# hand_brd.net
KiCad netlist of a schematic drawn in EAGLE
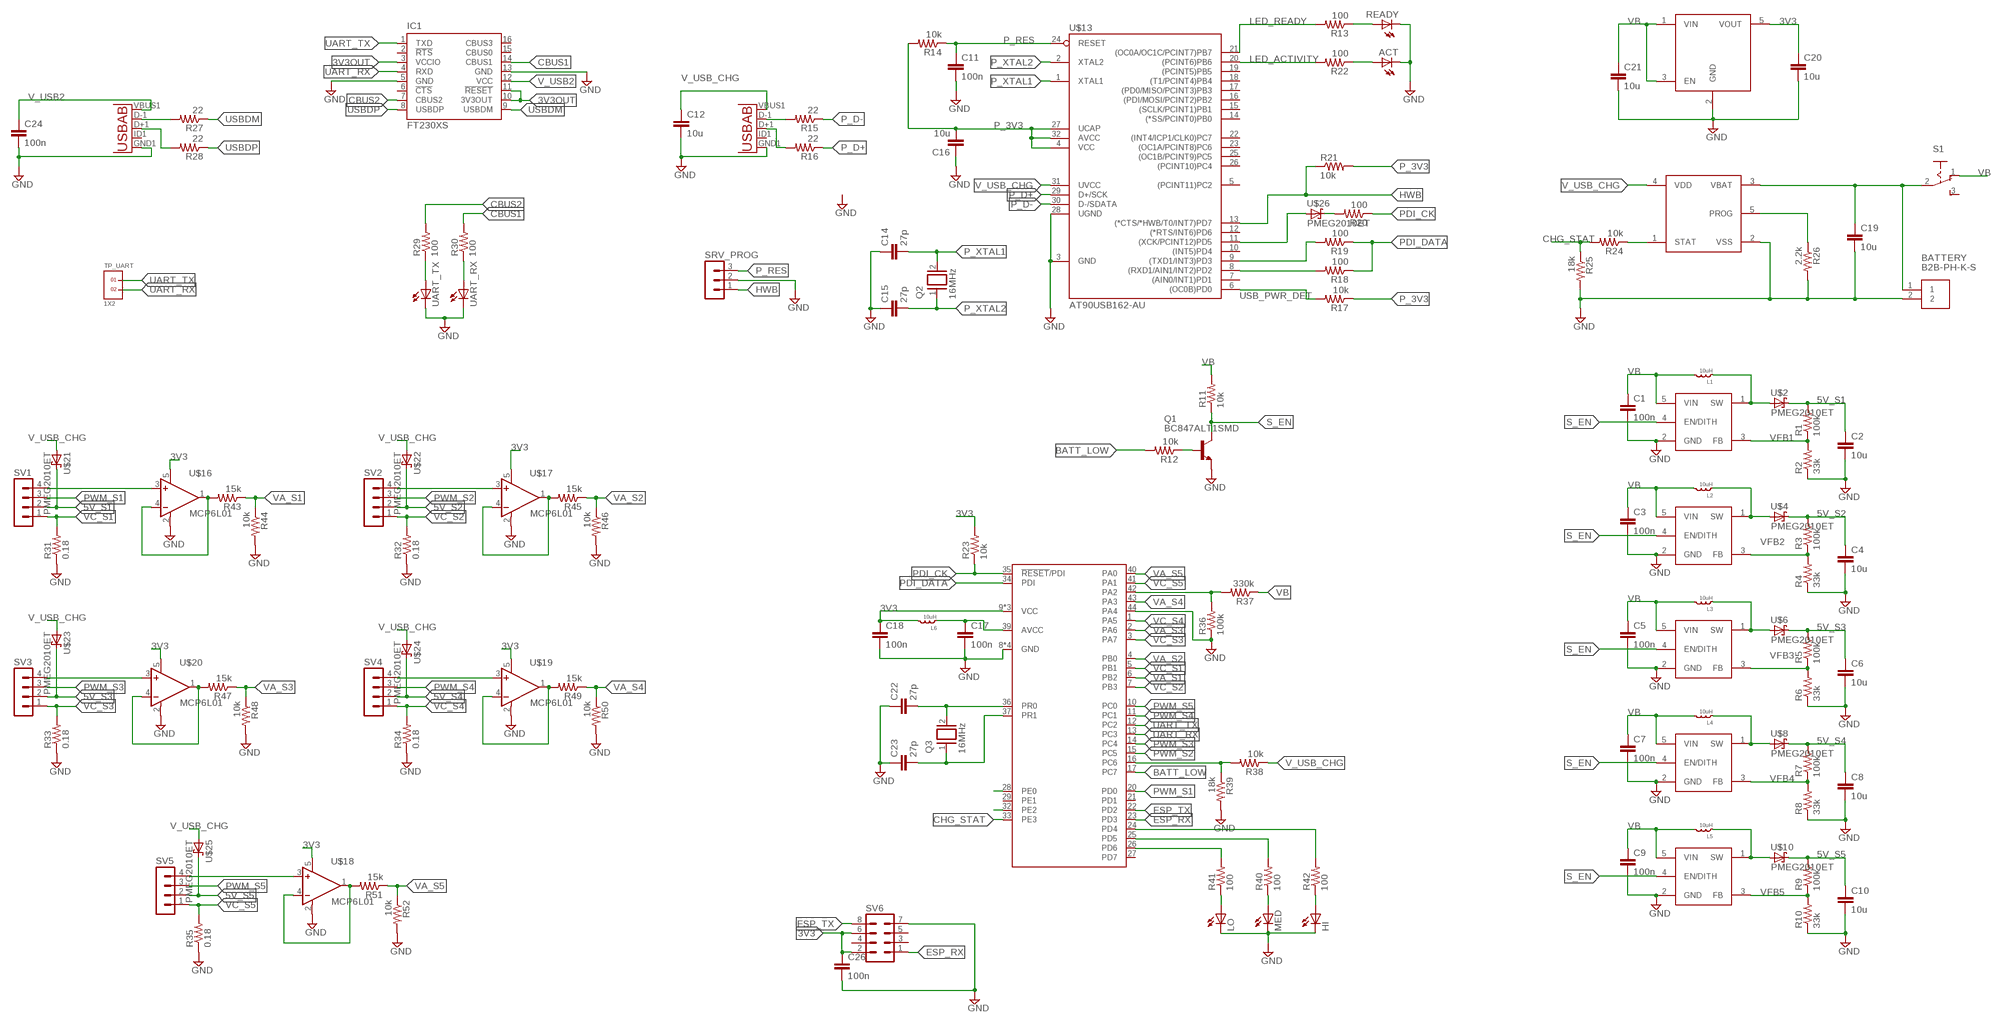
[diagram p0: schematic, sheet 1]

(export (version "E")
  (design (tool "Eeschema 10.0.6"))
  (components
    (comp (ref "ACT")
      (value "LEDCHIPLED_0805")
      (footprint "eagle-import:CHIPLED_0805")
      (libsource (lib "eagle-import") (part "LEDCHIPLED_0805"))
    )
    (comp (ref "BATTERY")
      (value "B2B-PH-K-S")
      (footprint "eagle-import:B2B-PH-K-S")
      (libsource (lib "eagle-import") (part "B2B-PH-K-S"))
    )
    (comp (ref "C1")
      (value "100n")
      (footprint "eagle-import:C0805K")
      (libsource (lib "eagle-import") (part "C-EUC0805K"))
    )
    (comp (ref "C2")
      (value "10u")
      (footprint "eagle-import:C0805K")
      (libsource (lib "eagle-import") (part "C-EUC0805K"))
    )
    (comp (ref "C3")
      (value "100n")
      (footprint "eagle-import:C0805K")
      (libsource (lib "eagle-import") (part "C-EUC0805K"))
    )
    (comp (ref "C4")
      (value "10u")
      (footprint "eagle-import:C0805K")
      (libsource (lib "eagle-import") (part "C-EUC0805K"))
    )
    (comp (ref "C5")
      (value "100n")
      (footprint "eagle-import:C0805K")
      (libsource (lib "eagle-import") (part "C-EUC0805K"))
    )
    (comp (ref "C6")
      (value "10u")
      (footprint "eagle-import:C0805K")
      (libsource (lib "eagle-import") (part "C-EUC0805K"))
    )
    (comp (ref "C7")
      (value "100n")
      (footprint "eagle-import:C0805K")
      (libsource (lib "eagle-import") (part "C-EUC0805K"))
    )
    (comp (ref "C8")
      (value "10u")
      (footprint "eagle-import:C0805K")
      (libsource (lib "eagle-import") (part "C-EUC0805K"))
    )
    (comp (ref "C9")
      (value "100n")
      (footprint "eagle-import:C0805K")
      (libsource (lib "eagle-import") (part "C-EUC0805K"))
    )
    (comp (ref "C10")
      (value "10u")
      (footprint "eagle-import:C0805K")
      (libsource (lib "eagle-import") (part "C-EUC0805K"))
    )
    (comp (ref "C11")
      (value "100n")
      (footprint "eagle-import:C0805K")
      (libsource (lib "eagle-import") (part "C-EUC0805K"))
    )
    (comp (ref "C12")
      (value "10u")
      (footprint "eagle-import:C0805K")
      (libsource (lib "eagle-import") (part "C-EUC0805K"))
    )
    (comp (ref "C14")
      (value "27p")
      (footprint "eagle-import:C0805K")
      (libsource (lib "eagle-import") (part "C-EUC0805K"))
    )
    (comp (ref "C15")
      (value "27p")
      (footprint "eagle-import:C0805K")
      (libsource (lib "eagle-import") (part "C-EUC0805K"))
    )
    (comp (ref "C16")
      (value "10u")
      (footprint "eagle-import:C0805K")
      (libsource (lib "eagle-import") (part "C-EUC0805K"))
    )
    (comp (ref "C17")
      (value "100n")
      (footprint "eagle-import:C0805K")
      (libsource (lib "eagle-import") (part "C-EUC0805K"))
    )
    (comp (ref "C18")
      (value "100n")
      (footprint "eagle-import:C0805K")
      (libsource (lib "eagle-import") (part "C-EUC0805K"))
    )
    (comp (ref "C19")
      (value "10u")
      (footprint "eagle-import:C0805K")
      (libsource (lib "eagle-import") (part "C-EUC0805K"))
    )
    (comp (ref "C20")
      (value "10u")
      (footprint "eagle-import:C0805K")
      (libsource (lib "eagle-import") (part "C-EUC0805K"))
    )
    (comp (ref "C21")
      (value "10u")
      (footprint "eagle-import:C0805K")
      (libsource (lib "eagle-import") (part "C-EUC0805K"))
    )
    (comp (ref "C22")
      (value "27p")
      (footprint "eagle-import:C0805K")
      (libsource (lib "eagle-import") (part "C-EUC0805K"))
    )
    (comp (ref "C23")
      (value "27p")
      (footprint "eagle-import:C0805K")
      (libsource (lib "eagle-import") (part "C-EUC0805K"))
    )
    (comp (ref "C24")
      (value "100n")
      (footprint "eagle-import:C0805K")
      (libsource (lib "eagle-import") (part "C-EUC0805K"))
    )
    (comp (ref "C26")
      (value "100n")
      (footprint "eagle-import:C0805K")
      (libsource (lib "eagle-import") (part "C-EUC0805K"))
    )
    (comp (ref "HI")
      (value "LEDCHIPLED_0805")
      (footprint "eagle-import:CHIPLED_0805")
      (libsource (lib "eagle-import") (part "LEDCHIPLED_0805"))
    )
    (comp (ref "IC1")
      (value "FT230XS")
      (footprint "eagle-import:SSOP16")
      (libsource (lib "eagle-import") (part "FT230XS"))
    )
    (comp (ref "L1")
      (value "10uH")
      (footprint "eagle-import:LTF5022")
      (libsource (lib "eagle-import") (part "L_TDK_LTF5022"))
    )
    (comp (ref "L2")
      (value "10uH")
      (footprint "eagle-import:LTF5022")
      (libsource (lib "eagle-import") (part "L_TDK_LTF5022"))
    )
    (comp (ref "L3")
      (value "10uH")
      (footprint "eagle-import:LTF5022")
      (libsource (lib "eagle-import") (part "L_TDK_LTF5022"))
    )
    (comp (ref "L4")
      (value "10uH")
      (footprint "eagle-import:LTF5022")
      (libsource (lib "eagle-import") (part "L_TDK_LTF5022"))
    )
    (comp (ref "L5")
      (value "10uH")
      (footprint "eagle-import:LTF5022")
      (libsource (lib "eagle-import") (part "L_TDK_LTF5022"))
    )
    (comp (ref "L6")
      (value "10uH")
      (footprint "eagle-import:LTF5022")
      (libsource (lib "eagle-import") (part "L_TDK_LTF5022"))
    )
    (comp (ref "LO")
      (value "LEDCHIPLED_0805")
      (footprint "eagle-import:CHIPLED_0805")
      (libsource (lib "eagle-import") (part "LEDCHIPLED_0805"))
    )
    (comp (ref "MED")
      (value "LEDCHIPLED_0805")
      (footprint "eagle-import:CHIPLED_0805")
      (libsource (lib "eagle-import") (part "LEDCHIPLED_0805"))
    )
    (comp (ref "Q1")
      (value "BC847ALT1SMD")
      (footprint "eagle-import:SOT23")
      (libsource (lib "eagle-import") (part "BC847SMDALT1"))
    )
    (comp (ref "Q2")
      (value "16MHz")
      (footprint "eagle-import:QS")
      (libsource (lib "eagle-import") (part "XTAL/S"))
    )
    (comp (ref "Q3")
      (value "16MHz")
      (footprint "eagle-import:QS")
      (libsource (lib "eagle-import") (part "XTAL/S"))
    )
    (comp (ref "R1")
      (value "100k")
      (footprint "eagle-import:M0805")
      (libsource (lib "eagle-import") (part "R-US_M0805"))
    )
    (comp (ref "R2")
      (value "33k")
      (footprint "eagle-import:M0805")
      (libsource (lib "eagle-import") (part "R-US_M0805"))
    )
    (comp (ref "R3")
      (value "100k")
      (footprint "eagle-import:M0805")
      (libsource (lib "eagle-import") (part "R-US_M0805"))
    )
    (comp (ref "R4")
      (value "33k")
      (footprint "eagle-import:M0805")
      (libsource (lib "eagle-import") (part "R-US_M0805"))
    )
    (comp (ref "R5")
      (value "100k")
      (footprint "eagle-import:M0805")
      (libsource (lib "eagle-import") (part "R-US_M0805"))
    )
    (comp (ref "R6")
      (value "33k")
      (footprint "eagle-import:M0805")
      (libsource (lib "eagle-import") (part "R-US_M0805"))
    )
    (comp (ref "R7")
      (value "100k")
      (footprint "eagle-import:M0805")
      (libsource (lib "eagle-import") (part "R-US_M0805"))
    )
    (comp (ref "R8")
      (value "33k")
      (footprint "eagle-import:M0805")
      (libsource (lib "eagle-import") (part "R-US_M0805"))
    )
    (comp (ref "R9")
      (value "100k")
      (footprint "eagle-import:M0805")
      (libsource (lib "eagle-import") (part "R-US_M0805"))
    )
    (comp (ref "R10")
      (value "33k")
      (footprint "eagle-import:M0805")
      (libsource (lib "eagle-import") (part "R-US_M0805"))
    )
    (comp (ref "R11")
      (value "10k")
      (footprint "eagle-import:M0805")
      (libsource (lib "eagle-import") (part "R-US_M0805"))
    )
    (comp (ref "R12")
      (value "10k")
      (footprint "eagle-import:M0805")
      (libsource (lib "eagle-import") (part "R-US_M0805"))
    )
    (comp (ref "R13")
      (value "100")
      (footprint "eagle-import:M0805")
      (libsource (lib "eagle-import") (part "R-US_M0805"))
    )
    (comp (ref "R14")
      (value "10k")
      (footprint "eagle-import:M0805")
      (libsource (lib "eagle-import") (part "R-US_M0805"))
    )
    (comp (ref "R15")
      (value "22")
      (footprint "eagle-import:M0805")
      (libsource (lib "eagle-import") (part "R-US_M0805"))
    )
    (comp (ref "R16")
      (value "22")
      (footprint "eagle-import:M0805")
      (libsource (lib "eagle-import") (part "R-US_M0805"))
    )
    (comp (ref "R17")
      (value "10k")
      (footprint "eagle-import:M0805")
      (libsource (lib "eagle-import") (part "R-US_M0805"))
    )
    (comp (ref "R18")
      (value "100")
      (footprint "eagle-import:M0805")
      (libsource (lib "eagle-import") (part "R-US_M0805"))
    )
    (comp (ref "R19")
      (value "100")
      (footprint "eagle-import:M0805")
      (libsource (lib "eagle-import") (part "R-US_M0805"))
    )
    (comp (ref "R20")
      (value "100")
      (footprint "eagle-import:M0805")
      (libsource (lib "eagle-import") (part "R-US_M0805"))
    )
    (comp (ref "R21")
      (value "10k")
      (footprint "eagle-import:M0805")
      (libsource (lib "eagle-import") (part "R-US_M0805"))
    )
    (comp (ref "R22")
      (value "100")
      (footprint "eagle-import:M0805")
      (libsource (lib "eagle-import") (part "R-US_M0805"))
    )
    (comp (ref "R23")
      (value "10k")
      (footprint "eagle-import:M0805")
      (libsource (lib "eagle-import") (part "R-US_M0805"))
    )
    (comp (ref "R24")
      (value "10k")
      (footprint "eagle-import:M0805")
      (libsource (lib "eagle-import") (part "R-US_M0805"))
    )
    (comp (ref "R25")
      (value "18k")
      (footprint "eagle-import:M0805")
      (libsource (lib "eagle-import") (part "R-US_M0805"))
    )
    (comp (ref "R26")
      (value "2.2k")
      (footprint "eagle-import:M0805")
      (libsource (lib "eagle-import") (part "R-US_M0805"))
    )
    (comp (ref "R27")
      (value "22")
      (footprint "eagle-import:M0805")
      (libsource (lib "eagle-import") (part "R-US_M0805"))
    )
    (comp (ref "R28")
      (value "22")
      (footprint "eagle-import:M0805")
      (libsource (lib "eagle-import") (part "R-US_M0805"))
    )
    (comp (ref "R29")
      (value "100")
      (footprint "eagle-import:M0805")
      (libsource (lib "eagle-import") (part "R-US_M0805"))
    )
    (comp (ref "R30")
      (value "100")
      (footprint "eagle-import:M0805")
      (libsource (lib "eagle-import") (part "R-US_M0805"))
    )
    (comp (ref "R31")
      (value "0.18")
      (footprint "eagle-import:M0805")
      (libsource (lib "eagle-import") (part "R-US_M0805"))
    )
    (comp (ref "R32")
      (value "0.18")
      (footprint "eagle-import:M0805")
      (libsource (lib "eagle-import") (part "R-US_M0805"))
    )
    (comp (ref "R33")
      (value "0.18")
      (footprint "eagle-import:M0805")
      (libsource (lib "eagle-import") (part "R-US_M0805"))
    )
    (comp (ref "R34")
      (value "0.18")
      (footprint "eagle-import:M0805")
      (libsource (lib "eagle-import") (part "R-US_M0805"))
    )
    (comp (ref "R35")
      (value "0.18")
      (footprint "eagle-import:M0805")
      (libsource (lib "eagle-import") (part "R-US_M0805"))
    )
    (comp (ref "R36")
      (value "100k")
      (footprint "eagle-import:M0805")
      (libsource (lib "eagle-import") (part "R-US_M0805"))
    )
    (comp (ref "R37")
      (value "330k")
      (footprint "eagle-import:M0805")
      (libsource (lib "eagle-import") (part "R-US_M0805"))
    )
    (comp (ref "R38")
      (value "10k")
      (footprint "eagle-import:M0805")
      (libsource (lib "eagle-import") (part "R-US_M0805"))
    )
    (comp (ref "R39")
      (value "18k")
      (footprint "eagle-import:M0805")
      (libsource (lib "eagle-import") (part "R-US_M0805"))
    )
    (comp (ref "R40")
      (value "100")
      (footprint "eagle-import:M0805")
      (libsource (lib "eagle-import") (part "R-US_M0805"))
    )
    (comp (ref "R41")
      (value "100")
      (footprint "eagle-import:M0805")
      (libsource (lib "eagle-import") (part "R-US_M0805"))
    )
    (comp (ref "R42")
      (value "100")
      (footprint "eagle-import:M0805")
      (libsource (lib "eagle-import") (part "R-US_M0805"))
    )
    (comp (ref "R43")
      (value "15k")
      (footprint "eagle-import:M0805")
      (libsource (lib "eagle-import") (part "R-US_M0805"))
    )
    (comp (ref "R44")
      (value "10k")
      (footprint "eagle-import:M0805")
      (libsource (lib "eagle-import") (part "R-US_M0805"))
    )
    (comp (ref "R45")
      (value "15k")
      (footprint "eagle-import:M0805")
      (libsource (lib "eagle-import") (part "R-US_M0805"))
    )
    (comp (ref "R46")
      (value "10k")
      (footprint "eagle-import:M0805")
      (libsource (lib "eagle-import") (part "R-US_M0805"))
    )
    (comp (ref "R47")
      (value "15k")
      (footprint "eagle-import:M0805")
      (libsource (lib "eagle-import") (part "R-US_M0805"))
    )
    (comp (ref "R48")
      (value "10k")
      (footprint "eagle-import:M0805")
      (libsource (lib "eagle-import") (part "R-US_M0805"))
    )
    (comp (ref "R49")
      (value "15k")
      (footprint "eagle-import:M0805")
      (libsource (lib "eagle-import") (part "R-US_M0805"))
    )
    (comp (ref "R50")
      (value "10k")
      (footprint "eagle-import:M0805")
      (libsource (lib "eagle-import") (part "R-US_M0805"))
    )
    (comp (ref "R51")
      (value "15k")
      (footprint "eagle-import:M0805")
      (libsource (lib "eagle-import") (part "R-US_M0805"))
    )
    (comp (ref "R52")
      (value "10k")
      (footprint "eagle-import:M0805")
      (libsource (lib "eagle-import") (part "R-US_M0805"))
    )
    (comp (ref "READY")
      (value "LEDCHIPLED_0805")
      (footprint "eagle-import:CHIPLED_0805")
      (libsource (lib "eagle-import") (part "LEDCHIPLED_0805"))
    )
    (comp (ref "S1")
      (value "255SB")
      (footprint "eagle-import:255SB")
      (libsource (lib "eagle-import") (part "255SB"))
    )
    (comp (ref "SRV_PROG")
      (value "MA03-1")
      (footprint "eagle-import:MA03-1")
      (libsource (lib "eagle-import") (part "MA03-1"))
    )
    (comp (ref "SV1")
      (value "MA04-1")
      (footprint "eagle-import:MA04-1")
      (libsource (lib "eagle-import") (part "MA04-1"))
    )
    (comp (ref "SV2")
      (value "MA04-1")
      (footprint "eagle-import:MA04-1")
      (libsource (lib "eagle-import") (part "MA04-1"))
    )
    (comp (ref "SV3")
      (value "MA04-1")
      (footprint "eagle-import:MA04-1")
      (libsource (lib "eagle-import") (part "MA04-1"))
    )
    (comp (ref "SV4")
      (value "MA04-1")
      (footprint "eagle-import:MA04-1")
      (libsource (lib "eagle-import") (part "MA04-1"))
    )
    (comp (ref "SV5")
      (value "MA04-1")
      (footprint "eagle-import:MA04-1")
      (libsource (lib "eagle-import") (part "MA04-1"))
    )
    (comp (ref "SV6")
      (value "MA04-2")
      (footprint "eagle-import:MA04-2")
      (libsource (lib "eagle-import") (part "MA04-2"))
    )
    (comp (ref "TP_UART")
      (value "1X2")
      (footprint "eagle-import:1X2")
      (libsource (lib "eagle-import") (part "1X2"))
    )
    (comp (ref "U$1")
      (value "MIC2250-2YD5")
      (footprint "eagle-import:SOT23-5")
      (libsource (lib "eagle-import") (part "MIC2250-2YD5"))
    )
    (comp (ref "U$2")
      (value "PMEG2010ET")
      (footprint "eagle-import:SOT23")
      (libsource (lib "eagle-import") (part "PMEG2010ET"))
    )
    (comp (ref "U$3")
      (value "MIC2250-2YD5")
      (footprint "eagle-import:SOT23-5")
      (libsource (lib "eagle-import") (part "MIC2250-2YD5"))
    )
    (comp (ref "U$4")
      (value "PMEG2010ET")
      (footprint "eagle-import:SOT23")
      (libsource (lib "eagle-import") (part "PMEG2010ET"))
    )
    (comp (ref "U$5")
      (value "MIC2250-2YD5")
      (footprint "eagle-import:SOT23-5")
      (libsource (lib "eagle-import") (part "MIC2250-2YD5"))
    )
    (comp (ref "U$6")
      (value "PMEG2010ET")
      (footprint "eagle-import:SOT23")
      (libsource (lib "eagle-import") (part "PMEG2010ET"))
    )
    (comp (ref "U$7")
      (value "MIC2250-2YD5")
      (footprint "eagle-import:SOT23-5")
      (libsource (lib "eagle-import") (part "MIC2250-2YD5"))
    )
    (comp (ref "U$8")
      (value "PMEG2010ET")
      (footprint "eagle-import:SOT23")
      (libsource (lib "eagle-import") (part "PMEG2010ET"))
    )
    (comp (ref "U$9")
      (value "MIC2250-2YD5")
      (footprint "eagle-import:SOT23-5")
      (libsource (lib "eagle-import") (part "MIC2250-2YD5"))
    )
    (comp (ref "U$10")
      (value "PMEG2010ET")
      (footprint "eagle-import:SOT23")
      (libsource (lib "eagle-import") (part "PMEG2010ET"))
    )
    (comp (ref "U$13")
      (value "AT90USB162-AU")
      (footprint "eagle-import:TQFP32-08")
      (libsource (lib "eagle-import") (part "AT90USB162-AU"))
    )
    (comp (ref "U$14")
      (value "MCP73831")
      (footprint "eagle-import:SOT23-5")
      (libsource (lib "eagle-import") (part "MCP73831"))
    )
    (comp (ref "U$15")
      (value "MIC5504")
      (footprint "eagle-import:SOT23-5")
      (libsource (lib "eagle-import") (part "MIC5504"))
    )
    (comp (ref "U$16")
      (value "MCP6L01")
      (footprint "eagle-import:SOT23-5")
      (libsource (lib "eagle-import") (part "MCP6L01"))
    )
    (comp (ref "U$17")
      (value "MCP6L01")
      (footprint "eagle-import:SOT23-5")
      (libsource (lib "eagle-import") (part "MCP6L01"))
    )
    (comp (ref "U$18")
      (value "MCP6L01")
      (footprint "eagle-import:SOT23-5")
      (libsource (lib "eagle-import") (part "MCP6L01"))
    )
    (comp (ref "U$19")
      (value "MCP6L01")
      (footprint "eagle-import:SOT23-5")
      (libsource (lib "eagle-import") (part "MCP6L01"))
    )
    (comp (ref "U$20")
      (value "MCP6L01")
      (footprint "eagle-import:SOT23-5")
      (libsource (lib "eagle-import") (part "MCP6L01"))
    )
    (comp (ref "U$21")
      (value "PMEG2010ET")
      (footprint "eagle-import:SOT23")
      (libsource (lib "eagle-import") (part "PMEG2010ET"))
    )
    (comp (ref "U$22")
      (value "PMEG2010ET")
      (footprint "eagle-import:SOT23")
      (libsource (lib "eagle-import") (part "PMEG2010ET"))
    )
    (comp (ref "U$23")
      (value "PMEG2010ET")
      (footprint "eagle-import:SOT23")
      (libsource (lib "eagle-import") (part "PMEG2010ET"))
    )
    (comp (ref "U$24")
      (value "PMEG2010ET")
      (footprint "eagle-import:SOT23")
      (libsource (lib "eagle-import") (part "PMEG2010ET"))
    )
    (comp (ref "U$25")
      (value "PMEG2010ET")
      (footprint "eagle-import:SOT23")
      (libsource (lib "eagle-import") (part "PMEG2010ET"))
    )
    (comp (ref "U$26")
      (value "PMEG2010ET")
      (footprint "eagle-import:SOT23")
      (libsource (lib "eagle-import") (part "PMEG2010ET"))
    )
    (comp (ref "U1")
      (value "USB\"\"")
      (footprint "eagle-import:USB-MICRO-SMD")
      (libsource (lib "eagle-import") (part "USB{dblquote}{dblquote}"))
    )
    (comp (ref "U2")
      (value "ATXMEGA128D4-AU")
      (footprint "eagle-import:TQFP-44A-44")
      (libsource (lib "eagle-import") (part "ATXMEGA128D4-AU"))
    )
    (comp (ref "U3")
      (value "USB\"\"")
      (footprint "eagle-import:USB-MICRO-SMD")
      (libsource (lib "eagle-import") (part "USB{dblquote}{dblquote}"))
    )
    (comp (ref "UART_RX")
      (value "LEDCHIPLED_0805")
      (footprint "eagle-import:CHIPLED_0805")
      (libsource (lib "eagle-import") (part "LEDCHIPLED_0805"))
    )
    (comp (ref "UART_TX")
      (value "LEDCHIPLED_0805")
      (footprint "eagle-import:CHIPLED_0805")
      (libsource (lib "eagle-import") (part "LEDCHIPLED_0805"))
    )
  )
  (nets
    (net (code "1") (name "/LED_ACTIVITY") (class "Default")
      (node (ref "R22") (pin "2") (pinfunction "2_2") (pintype "passive"))
      (node (ref "U$13") (pin "20") (pinfunction "(PCINT6)PB6_20") (pintype "bidirectional"))
    )
    (net (code "2") (name "/LED_READY") (class "Default")
      (node (ref "R13") (pin "2") (pinfunction "2_2") (pintype "passive"))
      (node (ref "U$13") (pin "21") (pinfunction "(OC0A/OC1C/PCINT7)PB7_21") (pintype "bidirectional"))
    )
    (net (code "3") (name "/USB_PWR_DET") (class "Default")
      (node (ref "R17") (pin "2") (pinfunction "2_2") (pintype "passive"))
      (node (ref "U$13") (pin "6") (pinfunction "(OC0B)PD0_6") (pintype "bidirectional"))
    )
    (net (code "4") (name "/VFB1") (class "Default")
      (node (ref "R1") (pin "1") (pinfunction "1_1") (pintype "passive"))
      (node (ref "R2") (pin "2") (pinfunction "2_2") (pintype "passive"))
      (node (ref "U$1") (pin "3") (pinfunction "FB_3") (pintype "bidirectional"))
    )
    (net (code "5") (name "/VFB2") (class "Default")
      (node (ref "R3") (pin "1") (pinfunction "1_1") (pintype "passive"))
      (node (ref "R4") (pin "2") (pinfunction "2_2") (pintype "passive"))
      (node (ref "U$3") (pin "3") (pinfunction "FB_3") (pintype "bidirectional"))
    )
    (net (code "6") (name "/VFB3") (class "Default")
      (node (ref "R5") (pin "1") (pinfunction "1_1") (pintype "passive"))
      (node (ref "R6") (pin "2") (pinfunction "2_2") (pintype "passive"))
      (node (ref "U$5") (pin "3") (pinfunction "FB_3") (pintype "bidirectional"))
    )
    (net (code "7") (name "/VFB4") (class "Default")
      (node (ref "R7") (pin "1") (pinfunction "1_1") (pintype "passive"))
      (node (ref "R8") (pin "2") (pinfunction "2_2") (pintype "passive"))
      (node (ref "U$7") (pin "3") (pinfunction "FB_3") (pintype "bidirectional"))
    )
    (net (code "8") (name "/VFB5") (class "Default")
      (node (ref "R10") (pin "2") (pinfunction "2_2") (pintype "passive"))
      (node (ref "R9") (pin "1") (pinfunction "1_1") (pintype "passive"))
      (node (ref "U$9") (pin "3") (pinfunction "FB_3") (pintype "bidirectional"))
    )
    (net (code "9") (name "3V3") (class "Default")
      (node (ref "C18") (pin "1") (pinfunction "1_1") (pintype "passive"))
      (node (ref "C20") (pin "1") (pinfunction "1_1") (pintype "passive"))
      (node (ref "C26") (pin "1") (pinfunction "1_1") (pintype "passive"))
      (node (ref "L6") (pin "P$2") (pinfunction "2_P$2") (pintype "passive"))
      (node (ref "R23") (pin "2") (pinfunction "2_2") (pintype "passive"))
      (node (ref "SV6") (pin "2") (pinfunction "2_2") (pintype "passive"))
      (node (ref "SV6") (pin "6") (pinfunction "6_6") (pintype "passive"))
      (node (ref "U$15") (pin "5") (pinfunction "VOUT_5") (pintype "bidirectional"))
      (node (ref "U$16") (pin "5") (pinfunction "V+_5") (pintype "power_in"))
      (node (ref "U$17") (pin "5") (pinfunction "V+_5") (pintype "power_in"))
      (node (ref "U$18") (pin "5") (pinfunction "V+_5") (pintype "power_in"))
      (node (ref "U$19") (pin "5") (pinfunction "V+_5") (pintype "power_in"))
      (node (ref "U$20") (pin "5") (pinfunction "V+_5") (pintype "power_in"))
      (node (ref "U2") (pin "19") (pinfunction "VCC_19") (pintype "power_in"))
      (node (ref "U2") (pin "31") (pinfunction "VCC_31") (pintype "power_in"))
      (node (ref "U2") (pin "9") (pinfunction "VCC_9") (pintype "power_in"))
    )
    (net (code "10") (name "3V3OUT") (class "Default")
      (node (ref "IC1") (pin "10") (pinfunction "3V3OUT_10") (pintype "output"))
      (node (ref "IC1") (pin "11") (pinfunction "~{RESET}_11") (pintype "input"))
      (node (ref "IC1") (pin "3") (pinfunction "VCCIO_3") (pintype "power_in"))
    )
    (net (code "11") (name "5V_S1") (class "Default")
      (node (ref "C2") (pin "1") (pinfunction "1_1") (pintype "passive"))
      (node (ref "R1") (pin "2") (pinfunction "2_2") (pintype "passive"))
      (node (ref "SV1") (pin "2") (pinfunction "2_2") (pintype "passive"))
      (node (ref "U$2") (pin "3") (pinfunction "C_3") (pintype "passive"))
      (node (ref "U$21") (pin "3") (pinfunction "C_3") (pintype "passive"))
    )
    (net (code "12") (name "5V_S2") (class "Default")
      (node (ref "C4") (pin "1") (pinfunction "1_1") (pintype "passive"))
      (node (ref "R3") (pin "2") (pinfunction "2_2") (pintype "passive"))
      (node (ref "SV2") (pin "2") (pinfunction "2_2") (pintype "passive"))
      (node (ref "U$22") (pin "3") (pinfunction "C_3") (pintype "passive"))
      (node (ref "U$4") (pin "3") (pinfunction "C_3") (pintype "passive"))
    )
    (net (code "13") (name "5V_S3") (class "Default")
      (node (ref "C6") (pin "1") (pinfunction "1_1") (pintype "passive"))
      (node (ref "R5") (pin "2") (pinfunction "2_2") (pintype "passive"))
      (node (ref "SV3") (pin "2") (pinfunction "2_2") (pintype "passive"))
      (node (ref "U$23") (pin "3") (pinfunction "C_3") (pintype "passive"))
      (node (ref "U$6") (pin "3") (pinfunction "C_3") (pintype "passive"))
    )
    (net (code "14") (name "5V_S4") (class "Default")
      (node (ref "C8") (pin "1") (pinfunction "1_1") (pintype "passive"))
      (node (ref "R7") (pin "2") (pinfunction "2_2") (pintype "passive"))
      (node (ref "SV4") (pin "2") (pinfunction "2_2") (pintype "passive"))
      (node (ref "U$24") (pin "3") (pinfunction "C_3") (pintype "passive"))
      (node (ref "U$8") (pin "3") (pinfunction "C_3") (pintype "passive"))
    )
    (net (code "15") (name "5V_S5") (class "Default")
      (node (ref "C10") (pin "1") (pinfunction "1_1") (pintype "passive"))
      (node (ref "R9") (pin "2") (pinfunction "2_2") (pintype "passive"))
      (node (ref "SV5") (pin "2") (pinfunction "2_2") (pintype "passive"))
      (node (ref "U$10") (pin "3") (pinfunction "C_3") (pintype "passive"))
      (node (ref "U$25") (pin "3") (pinfunction "C_3") (pintype "passive"))
    )
    (net (code "16") (name "BATT_LOW") (class "Default")
      (node (ref "R12") (pin "2") (pinfunction "2_2") (pintype "passive"))
      (node (ref "U2") (pin "17") (pinfunction "PC7_17") (pintype "bidirectional"))
    )
    (net (code "17") (name "CBUS1") (class "Default")
      (node (ref "IC1") (pin "14") (pinfunction "CBUS1_14") (pintype "bidirectional"))
      (node (ref "R30") (pin "2") (pinfunction "2_2") (pintype "passive"))
    )
    (net (code "18") (name "CBUS2") (class "Default")
      (node (ref "IC1") (pin "7") (pinfunction "CBUS2_7") (pintype "bidirectional"))
      (node (ref "R29") (pin "2") (pinfunction "2_2") (pintype "passive"))
    )
    (net (code "19") (name "CHG_STAT") (class "Default")
      (node (ref "R24") (pin "2") (pinfunction "2_2") (pintype "passive"))
      (node (ref "R25") (pin "1") (pinfunction "1_1") (pintype "passive"))
      (node (ref "U2") (pin "33") (pinfunction "PE3_33") (pintype "bidirectional"))
    )
    (net (code "20") (name "ESP_RX") (class "Default")
      (node (ref "SV6") (pin "1") (pinfunction "1_1") (pintype "passive"))
      (node (ref "U2") (pin "23") (pinfunction "PD3_23") (pintype "bidirectional"))
    )
    (net (code "21") (name "ESP_TX") (class "Default")
      (node (ref "SV6") (pin "8") (pinfunction "8_8") (pintype "passive"))
      (node (ref "U2") (pin "22") (pinfunction "PD2_22") (pintype "bidirectional"))
    )
    (net (code "22") (name "GND") (class "Default")
      (node (ref "ACT") (pin "C") (pinfunction "C_C") (pintype "passive"))
      (node (ref "BATTERY") (pin "2") (pinfunction "2_2") (pintype "bidirectional"))
      (node (ref "C1") (pin "2") (pinfunction "2_2") (pintype "passive"))
      (node (ref "C10") (pin "2") (pinfunction "2_2") (pintype "passive"))
      (node (ref "C11") (pin "2") (pinfunction "2_2") (pintype "passive"))
      (node (ref "C12") (pin "2") (pinfunction "2_2") (pintype "passive"))
      (node (ref "C14") (pin "1") (pinfunction "1_1") (pintype "passive"))
      (node (ref "C15") (pin "1") (pinfunction "1_1") (pintype "passive"))
      (node (ref "C16") (pin "1") (pinfunction "1_1") (pintype "passive"))
      (node (ref "C17") (pin "2") (pinfunction "2_2") (pintype "passive"))
      (node (ref "C18") (pin "2") (pinfunction "2_2") (pintype "passive"))
      (node (ref "C19") (pin "2") (pinfunction "2_2") (pintype "passive"))
      (node (ref "C2") (pin "2") (pinfunction "2_2") (pintype "passive"))
      (node (ref "C20") (pin "2") (pinfunction "2_2") (pintype "passive"))
      (node (ref "C21") (pin "2") (pinfunction "2_2") (pintype "passive"))
      (node (ref "C22") (pin "1") (pinfunction "1_1") (pintype "passive"))
      (node (ref "C23") (pin "1") (pinfunction "1_1") (pintype "passive"))
      (node (ref "C24") (pin "2") (pinfunction "2_2") (pintype "passive"))
      (node (ref "C26") (pin "2") (pinfunction "2_2") (pintype "passive"))
      (node (ref "C3") (pin "2") (pinfunction "2_2") (pintype "passive"))
      (node (ref "C4") (pin "2") (pinfunction "2_2") (pintype "passive"))
      (node (ref "C5") (pin "2") (pinfunction "2_2") (pintype "passive"))
      (node (ref "C6") (pin "2") (pinfunction "2_2") (pintype "passive"))
      (node (ref "C7") (pin "2") (pinfunction "2_2") (pintype "passive"))
      (node (ref "C8") (pin "2") (pinfunction "2_2") (pintype "passive"))
      (node (ref "C9") (pin "2") (pinfunction "2_2") (pintype "passive"))
      (node (ref "HI") (pin "C") (pinfunction "C_C") (pintype "passive"))
      (node (ref "IC1") (pin "13") (pinfunction "GND_13") (pintype "power_in"))
      (node (ref "IC1") (pin "5") (pinfunction "GND_5") (pintype "power_in"))
      (node (ref "LO") (pin "C") (pinfunction "C_C") (pintype "passive"))
      (node (ref "MED") (pin "C") (pinfunction "C_C") (pintype "passive"))
      (node (ref "Q1") (pin "2") (pinfunction "E_2") (pintype "passive"))
      (node (ref "R10") (pin "1") (pinfunction "1_1") (pintype "passive"))
      (node (ref "R2") (pin "1") (pinfunction "1_1") (pintype "passive"))
      (node (ref "R25") (pin "2") (pinfunction "2_2") (pintype "passive"))
      (node (ref "R26") (pin "2") (pinfunction "2_2") (pintype "passive"))
      (node (ref "R31") (pin "1") (pinfunction "1_1") (pintype "passive"))
      (node (ref "R32") (pin "1") (pinfunction "1_1") (pintype "passive"))
      (node (ref "R33") (pin "1") (pinfunction "1_1") (pintype "passive"))
      (node (ref "R34") (pin "1") (pinfunction "1_1") (pintype "passive"))
      (node (ref "R35") (pin "1") (pinfunction "1_1") (pintype "passive"))
      (node (ref "R36") (pin "1") (pinfunction "1_1") (pintype "passive"))
      (node (ref "R39") (pin "2") (pinfunction "2_2") (pintype "passive"))
      (node (ref "R4") (pin "1") (pinfunction "1_1") (pintype "passive"))
      (node (ref "R44") (pin "2") (pinfunction "2_2") (pintype "passive"))
      (node (ref "R46") (pin "2") (pinfunction "2_2") (pintype "passive"))
      (node (ref "R48") (pin "2") (pinfunction "2_2") (pintype "passive"))
      (node (ref "R50") (pin "2") (pinfunction "2_2") (pintype "passive"))
      (node (ref "R52") (pin "2") (pinfunction "2_2") (pintype "passive"))
      (node (ref "R6") (pin "1") (pinfunction "1_1") (pintype "passive"))
      (node (ref "R8") (pin "1") (pinfunction "1_1") (pintype "passive"))
      (node (ref "READY") (pin "C") (pinfunction "C_C") (pintype "passive"))
      (node (ref "SRV_PROG") (pin "2") (pinfunction "2_2") (pintype "passive"))
      (node (ref "SV6") (pin "7") (pinfunction "7_7") (pintype "passive"))
      (node (ref "U$1") (pin "2") (pinfunction "GND_2") (pintype "bidirectional"))
      (node (ref "U$13") (pin "28") (pinfunction "UGND_28") (pintype "power_in"))
      (node (ref "U$13") (pin "3") (pinfunction "GND_3") (pintype "power_in"))
      (node (ref "U$14") (pin "2") (pinfunction "VSS_2") (pintype "bidirectional"))
      (node (ref "U$15") (pin "2") (pinfunction "GND_2") (pintype "bidirectional"))
      (node (ref "U$16") (pin "2") (pinfunction "V-_2") (pintype "power_in"))
      (node (ref "U$17") (pin "2") (pinfunction "V-_2") (pintype "power_in"))
      (node (ref "U$18") (pin "2") (pinfunction "V-_2") (pintype "power_in"))
      (node (ref "U$19") (pin "2") (pinfunction "V-_2") (pintype "power_in"))
      (node (ref "U$20") (pin "2") (pinfunction "V-_2") (pintype "power_in"))
      (node (ref "U$3") (pin "2") (pinfunction "GND_2") (pintype "bidirectional"))
      (node (ref "U$5") (pin "2") (pinfunction "GND_2") (pintype "bidirectional"))
      (node (ref "U$7") (pin "2") (pinfunction "GND_2") (pintype "bidirectional"))
      (node (ref "U$9") (pin "2") (pinfunction "GND_2") (pintype "bidirectional"))
      (node (ref "U1") (pin "GND1") (pinfunction "GND_GND1") (pintype "bidirectional"))
      (node (ref "U2") (pin "18") (pinfunction "GND_18") (pintype "power_in"))
      (node (ref "U2") (pin "30") (pinfunction "GND_30") (pintype "power_in"))
      (node (ref "U2") (pin "38") (pinfunction "GND_38") (pintype "power_in"))
      (node (ref "U2") (pin "44") (pinfunction "PA4_44") (pintype "bidirectional"))
      (node (ref "U2") (pin "8") (pinfunction "GND_8") (pintype "power_in"))
      (node (ref "U3") (pin "GND1") (pinfunction "GND_GND1") (pintype "bidirectional"))
      (node (ref "UART_RX") (pin "C") (pinfunction "C_C") (pintype "passive"))
      (node (ref "UART_TX") (pin "C") (pinfunction "C_C") (pintype "passive"))
    )
    (net (code "23") (name "HWB") (class "Default")
      (node (ref "R21") (pin "1") (pinfunction "1_1") (pintype "passive"))
      (node (ref "SRV_PROG") (pin "1") (pinfunction "1_1") (pintype "passive"))
      (node (ref "U$13") (pin "13") (pinfunction "(*CTS/*HWB/T0/INT7)PD7_13") (pintype "bidirectional"))
    )
    (net (code "24") (name "Net-(ACT-PadA)") (class "Default")
      (node (ref "ACT") (pin "A") (pinfunction "A_A") (pintype "passive"))
      (node (ref "R22") (pin "1") (pinfunction "1_1") (pintype "passive"))
    )
    (net (code "25") (name "Net-(HI-PadA)") (class "Default")
      (node (ref "HI") (pin "A") (pinfunction "A_A") (pintype "passive"))
      (node (ref "R42") (pin "1") (pinfunction "1_1") (pintype "passive"))
    )
    (net (code "26") (name "Net-(L1-1)") (class "Default")
      (node (ref "L1") (pin "P$1") (pinfunction "1_P$1") (pintype "passive"))
      (node (ref "U$1") (pin "1") (pinfunction "SW_1") (pintype "bidirectional"))
      (node (ref "U$2") (pin "1") (pinfunction "A_1") (pintype "passive"))
    )
    (net (code "27") (name "Net-(L2-1)") (class "Default")
      (node (ref "L2") (pin "P$1") (pinfunction "1_P$1") (pintype "passive"))
      (node (ref "U$3") (pin "1") (pinfunction "SW_1") (pintype "bidirectional"))
      (node (ref "U$4") (pin "1") (pinfunction "A_1") (pintype "passive"))
    )
    (net (code "28") (name "Net-(L3-1)") (class "Default")
      (node (ref "L3") (pin "P$1") (pinfunction "1_P$1") (pintype "passive"))
      (node (ref "U$5") (pin "1") (pinfunction "SW_1") (pintype "bidirectional"))
      (node (ref "U$6") (pin "1") (pinfunction "A_1") (pintype "passive"))
    )
    (net (code "29") (name "Net-(L4-1)") (class "Default")
      (node (ref "L4") (pin "P$1") (pinfunction "1_P$1") (pintype "passive"))
      (node (ref "U$7") (pin "1") (pinfunction "SW_1") (pintype "bidirectional"))
      (node (ref "U$8") (pin "1") (pinfunction "A_1") (pintype "passive"))
    )
    (net (code "30") (name "Net-(L5-1)") (class "Default")
      (node (ref "L5") (pin "P$1") (pinfunction "1_P$1") (pintype "passive"))
      (node (ref "U$10") (pin "1") (pinfunction "A_1") (pintype "passive"))
      (node (ref "U$9") (pin "1") (pinfunction "SW_1") (pintype "bidirectional"))
    )
    (net (code "31") (name "Net-(L6-1)") (class "Default")
      (node (ref "C17") (pin "1") (pinfunction "1_1") (pintype "passive"))
      (node (ref "L6") (pin "P$1") (pinfunction "1_P$1") (pintype "passive"))
      (node (ref "U2") (pin "39") (pinfunction "AVCC_39") (pintype "power_in"))
    )
    (net (code "32") (name "Net-(LO-PadA)") (class "Default")
      (node (ref "LO") (pin "A") (pinfunction "A_A") (pintype "passive"))
      (node (ref "R41") (pin "1") (pinfunction "1_1") (pintype "passive"))
    )
    (net (code "33") (name "Net-(MED-PadA)") (class "Default")
      (node (ref "MED") (pin "A") (pinfunction "A_A") (pintype "passive"))
      (node (ref "R40") (pin "1") (pinfunction "1_1") (pintype "passive"))
    )
    (net (code "34") (name "Net-(Q1-B)") (class "Default")
      (node (ref "Q1") (pin "1") (pinfunction "B_1") (pintype "passive"))
      (node (ref "R12") (pin "1") (pinfunction "1_1") (pintype "passive"))
    )
    (net (code "35") (name "Net-(R13-Pad1)") (class "Default")
      (node (ref "R13") (pin "1") (pinfunction "1_1") (pintype "passive"))
      (node (ref "READY") (pin "A") (pinfunction "A_A") (pintype "passive"))
    )
    (net (code "36") (name "Net-(R29-Pad1)") (class "Default")
      (node (ref "R29") (pin "1") (pinfunction "1_1") (pintype "passive"))
      (node (ref "UART_TX") (pin "A") (pinfunction "A_A") (pintype "passive"))
    )
    (net (code "37") (name "Net-(R30-Pad1)") (class "Default")
      (node (ref "R30") (pin "1") (pinfunction "1_1") (pintype "passive"))
      (node (ref "UART_RX") (pin "A") (pinfunction "A_A") (pintype "passive"))
    )
    (net (code "38") (name "Net-(S1-P)") (class "Default")
      (node (ref "BATTERY") (pin "1") (pinfunction "1_1") (pintype "bidirectional"))
      (node (ref "C19") (pin "1") (pinfunction "1_1") (pintype "passive"))
      (node (ref "S1") (pin "2") (pinfunction "P_2") (pintype "passive"))
      (node (ref "U$14") (pin "3") (pinfunction "VBAT_3") (pintype "bidirectional"))
    )
    (net (code "39") (name "Net-(U$13-(RXD1{slash}AIN1{slash}INT2)PD2)") (class "Default")
      (node (ref "R18") (pin "2") (pinfunction "2_2") (pintype "passive"))
      (node (ref "U$13") (pin "8") (pinfunction "(RXD1/AIN1/INT2)PD2_8") (pintype "bidirectional"))
    )
    (net (code "40") (name "Net-(U$13-(TXD1{slash}INT3)PD3)") (class "Default")
      (node (ref "R19") (pin "2") (pinfunction "2_2") (pintype "passive"))
      (node (ref "U$13") (pin "9") (pinfunction "(TXD1/INT3)PD3_9") (pintype "bidirectional"))
    )
    (net (code "41") (name "Net-(U$13-(XCK{slash}PCINT12)PD5)") (class "Default")
      (node (ref "U$13") (pin "11") (pinfunction "(XCK/PCINT12)PD5_11") (pintype "bidirectional"))
      (node (ref "U$26") (pin "1") (pinfunction "A_1") (pintype "passive"))
    )
    (net (code "42") (name "Net-(U$14-PROG)") (class "Default")
      (node (ref "R26") (pin "1") (pinfunction "1_1") (pintype "passive"))
      (node (ref "U$14") (pin "5") (pinfunction "PROG_5") (pintype "bidirectional"))
    )
    (net (code "43") (name "Net-(U$14-STAT)") (class "Default")
      (node (ref "R24") (pin "1") (pinfunction "1_1") (pintype "passive"))
      (node (ref "U$14") (pin "1") (pinfunction "STAT_1") (pintype "bidirectional"))
    )
    (net (code "44") (name "Net-(U$16-+IN)") (class "Default")
      (node (ref "SV1") (pin "4") (pinfunction "4_4") (pintype "passive"))
      (node (ref "U$16") (pin "3") (pinfunction "+IN_3") (pintype "input"))
    )
    (net (code "45") (name "Net-(U$16--IN)") (class "Default")
      (node (ref "R43") (pin "2") (pinfunction "2_2") (pintype "passive"))
      (node (ref "U$16") (pin "1") (pinfunction "OUT_1") (pintype "output"))
      (node (ref "U$16") (pin "4") (pinfunction "-IN_4") (pintype "input"))
    )
    (net (code "46") (name "Net-(U$17-+IN)") (class "Default")
      (node (ref "SV2") (pin "4") (pinfunction "4_4") (pintype "passive"))
      (node (ref "U$17") (pin "3") (pinfunction "+IN_3") (pintype "input"))
    )
    (net (code "47") (name "Net-(U$17--IN)") (class "Default")
      (node (ref "R45") (pin "2") (pinfunction "2_2") (pintype "passive"))
      (node (ref "U$17") (pin "1") (pinfunction "OUT_1") (pintype "output"))
      (node (ref "U$17") (pin "4") (pinfunction "-IN_4") (pintype "input"))
    )
    (net (code "48") (name "Net-(U$18-+IN)") (class "Default")
      (node (ref "SV5") (pin "4") (pinfunction "4_4") (pintype "passive"))
      (node (ref "U$18") (pin "3") (pinfunction "+IN_3") (pintype "input"))
    )
    (net (code "49") (name "Net-(U$18--IN)") (class "Default")
      (node (ref "R51") (pin "2") (pinfunction "2_2") (pintype "passive"))
      (node (ref "U$18") (pin "1") (pinfunction "OUT_1") (pintype "output"))
      (node (ref "U$18") (pin "4") (pinfunction "-IN_4") (pintype "input"))
    )
    (net (code "50") (name "Net-(U$19-+IN)") (class "Default")
      (node (ref "SV4") (pin "4") (pinfunction "4_4") (pintype "passive"))
      (node (ref "U$19") (pin "3") (pinfunction "+IN_3") (pintype "input"))
    )
    (net (code "51") (name "Net-(U$19--IN)") (class "Default")
      (node (ref "R49") (pin "2") (pinfunction "2_2") (pintype "passive"))
      (node (ref "U$19") (pin "1") (pinfunction "OUT_1") (pintype "output"))
      (node (ref "U$19") (pin "4") (pinfunction "-IN_4") (pintype "input"))
    )
    (net (code "52") (name "Net-(U$20-+IN)") (class "Default")
      (node (ref "SV3") (pin "4") (pinfunction "4_4") (pintype "passive"))
      (node (ref "U$20") (pin "3") (pinfunction "+IN_3") (pintype "input"))
    )
    (net (code "53") (name "Net-(U$20--IN)") (class "Default")
      (node (ref "R47") (pin "2") (pinfunction "2_2") (pintype "passive"))
      (node (ref "U$20") (pin "1") (pinfunction "OUT_1") (pintype "output"))
      (node (ref "U$20") (pin "4") (pinfunction "-IN_4") (pintype "input"))
    )
    (net (code "54") (name "Net-(U$26-C)") (class "Default")
      (node (ref "R20") (pin "2") (pinfunction "2_2") (pintype "passive"))
      (node (ref "U$26") (pin "3") (pinfunction "C_3") (pintype "passive"))
    )
    (net (code "55") (name "Net-(U1-D+)") (class "Default")
      (node (ref "R28") (pin "2") (pinfunction "2_2") (pintype "passive"))
      (node (ref "U1") (pin "D+1") (pinfunction "D+_D+1") (pintype "bidirectional"))
    )
    (net (code "56") (name "Net-(U1-D-)") (class "Default")
      (node (ref "R27") (pin "2") (pinfunction "2_2") (pintype "passive"))
      (node (ref "U1") (pin "D-1") (pinfunction "D-_D-1") (pintype "bidirectional"))
    )
    (net (code "57") (name "Net-(U2-PA2)") (class "Default")
      (node (ref "R36") (pin "2") (pinfunction "2_2") (pintype "passive"))
      (node (ref "R37") (pin "2") (pinfunction "2_2") (pintype "passive"))
      (node (ref "U2") (pin "42") (pinfunction "PA2_42") (pintype "bidirectional"))
    )
    (net (code "58") (name "Net-(U2-PC6)") (class "Default")
      (node (ref "R38") (pin "2") (pinfunction "2_2") (pintype "passive"))
      (node (ref "R39") (pin "1") (pinfunction "1_1") (pintype "passive"))
      (node (ref "U2") (pin "16") (pinfunction "PC6_16") (pintype "bidirectional"))
    )
    (net (code "59") (name "Net-(U2-PD4)") (class "Default")
      (node (ref "R42") (pin "2") (pinfunction "2_2") (pintype "passive"))
      (node (ref "U2") (pin "24") (pinfunction "PD4_24") (pintype "bidirectional"))
    )
    (net (code "60") (name "Net-(U2-PD5)") (class "Default")
      (node (ref "R40") (pin "2") (pinfunction "2_2") (pintype "passive"))
      (node (ref "U2") (pin "25") (pinfunction "PD5_25") (pintype "bidirectional"))
    )
    (net (code "61") (name "Net-(U2-PD6)") (class "Default")
      (node (ref "R41") (pin "2") (pinfunction "2_2") (pintype "passive"))
      (node (ref "U2") (pin "26") (pinfunction "PD6_26") (pintype "bidirectional"))
    )
    (net (code "62") (name "Net-(U2-PR0)") (class "Default")
      (node (ref "C22") (pin "2") (pinfunction "2_2") (pintype "passive"))
      (node (ref "Q3") (pin "2") (pinfunction "2_2") (pintype "passive"))
      (node (ref "U2") (pin "36") (pinfunction "PR0_36") (pintype "bidirectional"))
    )
    (net (code "63") (name "Net-(U2-PR1)") (class "Default")
      (node (ref "C23") (pin "2") (pinfunction "2_2") (pintype "passive"))
      (node (ref "Q3") (pin "1") (pinfunction "1_1") (pintype "passive"))
      (node (ref "U2") (pin "37") (pinfunction "PR1_37") (pintype "bidirectional"))
    )
    (net (code "64") (name "Net-(U3-D+)") (class "Default")
      (node (ref "R16") (pin "2") (pinfunction "2_2") (pintype "passive"))
      (node (ref "U3") (pin "D+1") (pinfunction "D+_D+1") (pintype "bidirectional"))
    )
    (net (code "65") (name "Net-(U3-D-)") (class "Default")
      (node (ref "R15") (pin "2") (pinfunction "2_2") (pintype "passive"))
      (node (ref "U3") (pin "D-1") (pinfunction "D-_D-1") (pintype "bidirectional"))
    )
    (net (code "66") (name "PDI_CK") (class "Default")
      (node (ref "R20") (pin "1") (pinfunction "1_1") (pintype "passive"))
      (node (ref "R23") (pin "1") (pinfunction "1_1") (pintype "passive"))
      (node (ref "U2") (pin "35") (pinfunction "~{RESET}/PDI_35") (pintype "bidirectional"))
    )
    (net (code "67") (name "PDI_DATA") (class "Default")
      (node (ref "R18") (pin "1") (pinfunction "1_1") (pintype "passive"))
      (node (ref "R19") (pin "1") (pinfunction "1_1") (pintype "passive"))
      (node (ref "U2") (pin "34") (pinfunction "PDI_34") (pintype "bidirectional"))
    )
    (net (code "68") (name "PWM_S1") (class "Default")
      (node (ref "SV1") (pin "3") (pinfunction "3_3") (pintype "passive"))
      (node (ref "U2") (pin "20") (pinfunction "PD0_20") (pintype "bidirectional"))
    )
    (net (code "69") (name "PWM_S2") (class "Default")
      (node (ref "SV2") (pin "3") (pinfunction "3_3") (pintype "passive"))
      (node (ref "U2") (pin "15") (pinfunction "PC5_15") (pintype "bidirectional"))
    )
    (net (code "70") (name "PWM_S3") (class "Default")
      (node (ref "SV3") (pin "3") (pinfunction "3_3") (pintype "passive"))
      (node (ref "U2") (pin "14") (pinfunction "PC4_14") (pintype "bidirectional"))
    )
    (net (code "71") (name "PWM_S4") (class "Default")
      (node (ref "SV4") (pin "3") (pinfunction "3_3") (pintype "passive"))
      (node (ref "U2") (pin "11") (pinfunction "PC1_11") (pintype "bidirectional"))
    )
    (net (code "72") (name "PWM_S5") (class "Default")
      (node (ref "SV5") (pin "3") (pinfunction "3_3") (pintype "passive"))
      (node (ref "U2") (pin "10") (pinfunction "PC0_10") (pintype "bidirectional"))
    )
    (net (code "73") (name "P_3V3") (class "Default")
      (node (ref "C16") (pin "2") (pinfunction "2_2") (pintype "passive"))
      (node (ref "R14") (pin "2") (pinfunction "2_2") (pintype "passive"))
      (node (ref "R17") (pin "1") (pinfunction "1_1") (pintype "passive"))
      (node (ref "R21") (pin "2") (pinfunction "2_2") (pintype "passive"))
      (node (ref "U$13") (pin "27") (pinfunction "UCAP_27") (pintype "power_in"))
      (node (ref "U$13") (pin "32") (pinfunction "AVCC_32") (pintype "power_in"))
      (node (ref "U$13") (pin "4") (pinfunction "VCC_4") (pintype "power_in"))
    )
    (net (code "74") (name "P_D+") (class "Default")
      (node (ref "R16") (pin "1") (pinfunction "1_1") (pintype "passive"))
      (node (ref "U$13") (pin "29") (pinfunction "D+/SCK_29") (pintype "bidirectional"))
    )
    (net (code "75") (name "P_D-") (class "Default")
      (node (ref "R15") (pin "1") (pinfunction "1_1") (pintype "passive"))
      (node (ref "U$13") (pin "30") (pinfunction "D-/SDATA_30") (pintype "bidirectional"))
    )
    (net (code "76") (name "P_RES") (class "Default")
      (node (ref "C11") (pin "1") (pinfunction "1_1") (pintype "passive"))
      (node (ref "R14") (pin "1") (pinfunction "1_1") (pintype "passive"))
      (node (ref "SRV_PROG") (pin "3") (pinfunction "3_3") (pintype "passive"))
      (node (ref "U$13") (pin "24") (pinfunction "RESET_24") (pintype "input"))
    )
    (net (code "77") (name "P_XTAL1") (class "Default")
      (node (ref "C14") (pin "2") (pinfunction "2_2") (pintype "passive"))
      (node (ref "Q2") (pin "2") (pinfunction "2_2") (pintype "passive"))
      (node (ref "U$13") (pin "1") (pinfunction "XTAL1_1") (pintype "bidirectional"))
    )
    (net (code "78") (name "P_XTAL2") (class "Default")
      (node (ref "C15") (pin "2") (pinfunction "2_2") (pintype "passive"))
      (node (ref "Q2") (pin "1") (pinfunction "1_1") (pintype "passive"))
      (node (ref "U$13") (pin "2") (pinfunction "XTAL2_2") (pintype "bidirectional"))
    )
    (net (code "79") (name "S_EN") (class "Default")
      (node (ref "Q1") (pin "3") (pinfunction "C_3") (pintype "passive"))
      (node (ref "R11") (pin "1") (pinfunction "1_1") (pintype "passive"))
      (node (ref "U$1") (pin "4") (pinfunction "EN/DITH_4") (pintype "bidirectional"))
      (node (ref "U$3") (pin "4") (pinfunction "EN/DITH_4") (pintype "bidirectional"))
      (node (ref "U$5") (pin "4") (pinfunction "EN/DITH_4") (pintype "bidirectional"))
      (node (ref "U$7") (pin "4") (pinfunction "EN/DITH_4") (pintype "bidirectional"))
      (node (ref "U$9") (pin "4") (pinfunction "EN/DITH_4") (pintype "bidirectional"))
    )
    (net (code "80") (name "UART_RX") (class "Default")
      (node (ref "IC1") (pin "4") (pinfunction "RXD_4") (pintype "input"))
      (node (ref "TP_UART") (pin "2") (pinfunction "2_2") (pintype "bidirectional"))
      (node (ref "U2") (pin "13") (pinfunction "PC3_13") (pintype "bidirectional"))
    )
    (net (code "81") (name "UART_TX") (class "Default")
      (node (ref "IC1") (pin "1") (pinfunction "TXD_1") (pintype "output"))
      (node (ref "TP_UART") (pin "1") (pinfunction "1_1") (pintype "bidirectional"))
      (node (ref "U2") (pin "12") (pinfunction "PC2_12") (pintype "bidirectional"))
    )
    (net (code "82") (name "USBDM") (class "Default")
      (node (ref "IC1") (pin "9") (pinfunction "USBDM_9") (pintype "input"))
      (node (ref "R27") (pin "1") (pinfunction "1_1") (pintype "passive"))
    )
    (net (code "83") (name "USBDP") (class "Default")
      (node (ref "IC1") (pin "8") (pinfunction "USBDP_8") (pintype "input"))
      (node (ref "R28") (pin "1") (pinfunction "1_1") (pintype "passive"))
    )
    (net (code "84") (name "VA_S1") (class "Default")
      (node (ref "R43") (pin "1") (pinfunction "1_1") (pintype "passive"))
      (node (ref "R44") (pin "1") (pinfunction "1_1") (pintype "passive"))
      (node (ref "U2") (pin "6") (pinfunction "PB2_6") (pintype "bidirectional"))
    )
    (net (code "85") (name "VA_S2") (class "Default")
      (node (ref "R45") (pin "1") (pinfunction "1_1") (pintype "passive"))
      (node (ref "R46") (pin "1") (pinfunction "1_1") (pintype "passive"))
      (node (ref "U2") (pin "4") (pinfunction "PB0_4") (pintype "bidirectional"))
    )
    (net (code "86") (name "VA_S3") (class "Default")
      (node (ref "R47") (pin "1") (pinfunction "1_1") (pintype "passive"))
      (node (ref "R48") (pin "1") (pinfunction "1_1") (pintype "passive"))
      (node (ref "U2") (pin "2") (pinfunction "PA6_2") (pintype "bidirectional"))
    )
    (net (code "87") (name "VA_S4") (class "Default")
      (node (ref "R49") (pin "1") (pinfunction "1_1") (pintype "passive"))
      (node (ref "R50") (pin "1") (pinfunction "1_1") (pintype "passive"))
      (node (ref "U2") (pin "43") (pinfunction "PA3_43") (pintype "bidirectional"))
    )
    (net (code "88") (name "VA_S5") (class "Default")
      (node (ref "R51") (pin "1") (pinfunction "1_1") (pintype "passive"))
      (node (ref "R52") (pin "1") (pinfunction "1_1") (pintype "passive"))
      (node (ref "U2") (pin "40") (pinfunction "PA0_40") (pintype "bidirectional"))
    )
    (net (code "89") (name "VB") (class "Default")
      (node (ref "C1") (pin "1") (pinfunction "1_1") (pintype "passive"))
      (node (ref "C21") (pin "1") (pinfunction "1_1") (pintype "passive"))
      (node (ref "C3") (pin "1") (pinfunction "1_1") (pintype "passive"))
      (node (ref "C5") (pin "1") (pinfunction "1_1") (pintype "passive"))
      (node (ref "C7") (pin "1") (pinfunction "1_1") (pintype "passive"))
      (node (ref "C9") (pin "1") (pinfunction "1_1") (pintype "passive"))
      (node (ref "L1") (pin "P$2") (pinfunction "2_P$2") (pintype "passive"))
      (node (ref "L2") (pin "P$2") (pinfunction "2_P$2") (pintype "passive"))
      (node (ref "L3") (pin "P$2") (pinfunction "2_P$2") (pintype "passive"))
      (node (ref "L4") (pin "P$2") (pinfunction "2_P$2") (pintype "passive"))
      (node (ref "L5") (pin "P$2") (pinfunction "2_P$2") (pintype "passive"))
      (node (ref "R11") (pin "2") (pinfunction "2_2") (pintype "passive"))
      (node (ref "R37") (pin "1") (pinfunction "1_1") (pintype "passive"))
      (node (ref "S1") (pin "1") (pinfunction "O_1") (pintype "passive"))
      (node (ref "U$1") (pin "5") (pinfunction "VIN_5") (pintype "bidirectional"))
      (node (ref "U$15") (pin "1") (pinfunction "VIN_1") (pintype "bidirectional"))
      (node (ref "U$15") (pin "3") (pinfunction "EN_3") (pintype "bidirectional"))
      (node (ref "U$3") (pin "5") (pinfunction "VIN_5") (pintype "bidirectional"))
      (node (ref "U$5") (pin "5") (pinfunction "VIN_5") (pintype "bidirectional"))
      (node (ref "U$7") (pin "5") (pinfunction "VIN_5") (pintype "bidirectional"))
      (node (ref "U$9") (pin "5") (pinfunction "VIN_5") (pintype "bidirectional"))
    )
    (net (code "90") (name "VC_S1") (class "Default")
      (node (ref "R31") (pin "2") (pinfunction "2_2") (pintype "passive"))
      (node (ref "SV1") (pin "1") (pinfunction "1_1") (pintype "passive"))
      (node (ref "U2") (pin "5") (pinfunction "PB1_5") (pintype "bidirectional"))
    )
    (net (code "91") (name "VC_S2") (class "Default")
      (node (ref "R32") (pin "2") (pinfunction "2_2") (pintype "passive"))
      (node (ref "SV2") (pin "1") (pinfunction "1_1") (pintype "passive"))
      (node (ref "U2") (pin "7") (pinfunction "PB3_7") (pintype "bidirectional"))
    )
    (net (code "92") (name "VC_S3") (class "Default")
      (node (ref "R33") (pin "2") (pinfunction "2_2") (pintype "passive"))
      (node (ref "SV3") (pin "1") (pinfunction "1_1") (pintype "passive"))
      (node (ref "U2") (pin "3") (pinfunction "PA7_3") (pintype "bidirectional"))
    )
    (net (code "93") (name "VC_S4") (class "Default")
      (node (ref "R34") (pin "2") (pinfunction "2_2") (pintype "passive"))
      (node (ref "SV4") (pin "1") (pinfunction "1_1") (pintype "passive"))
      (node (ref "U2") (pin "1") (pinfunction "PA5_1") (pintype "bidirectional"))
    )
    (net (code "94") (name "VC_S5") (class "Default")
      (node (ref "R35") (pin "2") (pinfunction "2_2") (pintype "passive"))
      (node (ref "SV5") (pin "1") (pinfunction "1_1") (pintype "passive"))
      (node (ref "U2") (pin "41") (pinfunction "PA1_41") (pintype "bidirectional"))
    )
    (net (code "95") (name "V_USB2") (class "Default")
      (node (ref "C24") (pin "1") (pinfunction "1_1") (pintype "passive"))
      (node (ref "IC1") (pin "12") (pinfunction "VCC_12") (pintype "power_in"))
      (node (ref "U1") (pin "VBUS1") (pinfunction "VBUS_VBUS1") (pintype "bidirectional"))
    )
    (net (code "96") (name "V_USB_CHG") (class "Default")
      (node (ref "C12") (pin "1") (pinfunction "1_1") (pintype "passive"))
      (node (ref "R38") (pin "1") (pinfunction "1_1") (pintype "passive"))
      (node (ref "U$13") (pin "31") (pinfunction "UVCC_31") (pintype "power_in"))
      (node (ref "U$14") (pin "4") (pinfunction "VDD_4") (pintype "bidirectional"))
      (node (ref "U$21") (pin "1") (pinfunction "A_1") (pintype "passive"))
      (node (ref "U$22") (pin "1") (pinfunction "A_1") (pintype "passive"))
      (node (ref "U$23") (pin "1") (pinfunction "A_1") (pintype "passive"))
      (node (ref "U$24") (pin "1") (pinfunction "A_1") (pintype "passive"))
      (node (ref "U$25") (pin "1") (pinfunction "A_1") (pintype "passive"))
      (node (ref "U3") (pin "VBUS1") (pinfunction "VBUS_VBUS1") (pintype "bidirectional"))
    )
    (net (code "97") (name "unconnected-(IC1-CBUS0-Pad15)") (class "Default")
      (node (ref "IC1") (pin "15") (pinfunction "CBUS0_15") (pintype "bidirectional"))
    )
    (net (code "98") (name "unconnected-(IC1-CBUS3-Pad16)") (class "Default")
      (node (ref "IC1") (pin "16") (pinfunction "CBUS3_16") (pintype "bidirectional"))
    )
    (net (code "99") (name "unconnected-(IC1-~{CTS}-Pad6)") (class "Default")
      (node (ref "IC1") (pin "6") (pinfunction "~{CTS}_6") (pintype "input"))
    )
    (net (code "100") (name "unconnected-(IC1-~{RTS}-Pad2)") (class "Default")
      (node (ref "IC1") (pin "2") (pinfunction "~{RTS}_2") (pintype "output"))
    )
    (net (code "101") (name "unconnected-(S1-S-Pad3)") (class "Default")
      (node (ref "S1") (pin "3") (pinfunction "S_3") (pintype "passive"))
    )
    (net (code "102") (name "unconnected-(SV6-Pad3)") (class "Default")
      (node (ref "SV6") (pin "3") (pinfunction "3_3") (pintype "passive"))
    )
    (net (code "103") (name "unconnected-(SV6-Pad4)") (class "Default")
      (node (ref "SV6") (pin "4") (pinfunction "4_4") (pintype "passive"))
    )
    (net (code "104") (name "unconnected-(SV6-Pad5)") (class "Default")
      (node (ref "SV6") (pin "5") (pinfunction "5_5") (pintype "passive"))
    )
    (net (code "105") (name "unconnected-(U$13-(*RTS{slash}INT6)PD6-Pad12)") (class "Default")
      (node (ref "U$13") (pin "12") (pinfunction "(*RTS/INT6)PD6_12") (pintype "bidirectional"))
    )
    (net (code "106") (name "unconnected-(U$13-(*SS{slash}PCINT0)PB0-Pad14)") (class "Default")
      (node (ref "U$13") (pin "14") (pinfunction "(*SS/PCINT0)PB0_14") (pintype "bidirectional"))
    )
    (net (code "107") (name "unconnected-(U$13-(AIN0{slash}INT1)PD1-Pad7)") (class "Default")
      (node (ref "U$13") (pin "7") (pinfunction "(AIN0/INT1)PD1_7") (pintype "bidirectional"))
    )
    (net (code "108") (name "unconnected-(U$13-(INT4{slash}ICP1{slash}CLK0)PC7-Pad22)") (class "Default")
      (node (ref "U$13") (pin "22") (pinfunction "(INT4/ICP1/CLK0)PC7_22") (pintype "bidirectional"))
    )
    (net (code "109") (name "unconnected-(U$13-(INT5)PD4-Pad10)") (class "Default")
      (node (ref "U$13") (pin "10") (pinfunction "(INT5)PD4_10") (pintype "bidirectional"))
    )
    (net (code "110") (name "unconnected-(U$13-(OC1A{slash}PCINT8)PC6-Pad23)") (class "Default")
      (node (ref "U$13") (pin "23") (pinfunction "(OC1A/PCINT8)PC6_23") (pintype "bidirectional"))
    )
    (net (code "111") (name "unconnected-(U$13-(OC1B{slash}PCINT9)PC5-Pad25)") (class "Default")
      (node (ref "U$13") (pin "25") (pinfunction "(OC1B/PCINT9)PC5_25") (pintype "bidirectional"))
    )
    (net (code "112") (name "unconnected-(U$13-(PCINT5)PB5-Pad19)") (class "Default")
      (node (ref "U$13") (pin "19") (pinfunction "(PCINT5)PB5_19") (pintype "bidirectional"))
    )
    (net (code "113") (name "unconnected-(U$13-(PCINT10)PC4-Pad26)") (class "Default")
      (node (ref "U$13") (pin "26") (pinfunction "(PCINT10)PC4_26") (pintype "bidirectional"))
    )
    (net (code "114") (name "unconnected-(U$13-(PCINT11)PC2-Pad5)") (class "Default")
      (node (ref "U$13") (pin "5") (pinfunction "(PCINT11)PC2_5") (pintype "bidirectional"))
    )
    (net (code "115") (name "unconnected-(U$13-(PD0{slash}MISO{slash}PCINT3)PB3-Pad17)") (class "Default")
      (node (ref "U$13") (pin "17") (pinfunction "(PD0/MISO/PCINT3)PB3_17") (pintype "bidirectional"))
    )
    (net (code "116") (name "unconnected-(U$13-(PDI{slash}MOSI{slash}PCINT2)PB2-Pad16)") (class "Default")
      (node (ref "U$13") (pin "16") (pinfunction "(PDI/MOSI/PCINT2)PB2_16") (pintype "bidirectional"))
    )
    (net (code "117") (name "unconnected-(U$13-(SCLK{slash}PCINT1)PB1-Pad15)") (class "Default")
      (node (ref "U$13") (pin "15") (pinfunction "(SCLK/PCINT1)PB1_15") (pintype "bidirectional"))
    )
    (net (code "118") (name "unconnected-(U$13-(T1{slash}PCINT4)PB4-Pad18)") (class "Default")
      (node (ref "U$13") (pin "18") (pinfunction "(T1/PCINT4)PB4_18") (pintype "bidirectional"))
    )
    (net (code "119") (name "unconnected-(U1-USBID-PadID1)") (class "Default")
      (node (ref "U1") (pin "ID1") (pinfunction "USBID_ID1") (pintype "bidirectional"))
    )
    (net (code "120") (name "unconnected-(U2-PD1-Pad21)") (class "Default")
      (node (ref "U2") (pin "21") (pinfunction "PD1_21") (pintype "bidirectional"))
    )
    (net (code "121") (name "unconnected-(U2-PD7-Pad27)") (class "Default")
      (node (ref "U2") (pin "27") (pinfunction "PD7_27") (pintype "bidirectional"))
    )
    (net (code "122") (name "unconnected-(U2-PE0-Pad28)") (class "Default")
      (node (ref "U2") (pin "28") (pinfunction "PE0_28") (pintype "bidirectional"))
    )
    (net (code "123") (name "unconnected-(U2-PE1-Pad29)") (class "Default")
      (node (ref "U2") (pin "29") (pinfunction "PE1_29") (pintype "bidirectional"))
    )
    (net (code "124") (name "unconnected-(U2-PE2-Pad32)") (class "Default")
      (node (ref "U2") (pin "32") (pinfunction "PE2_32") (pintype "bidirectional"))
    )
    (net (code "125") (name "unconnected-(U3-USBID-PadID1)") (class "Default")
      (node (ref "U3") (pin "ID1") (pinfunction "USBID_ID1") (pintype "bidirectional"))
    )
  )
)
